# Schemat_JD.net
KiCad netlist of a schematic drawn in Altium Designer
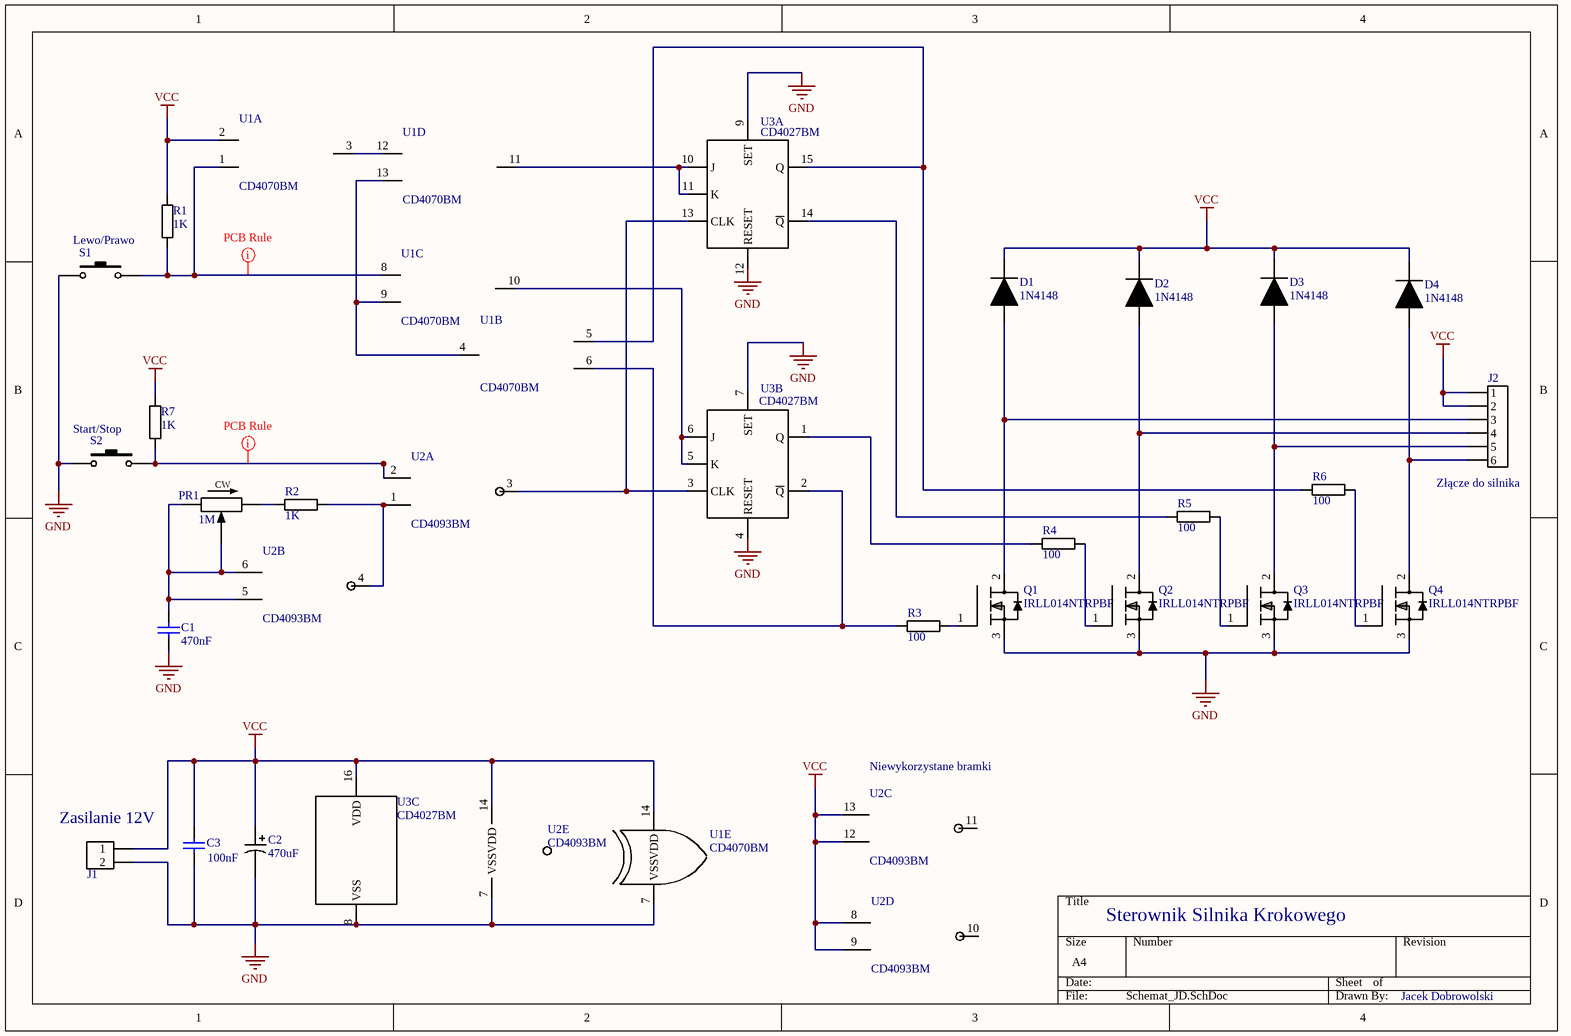
[diagram p0: Schemat_JD.SchDoc]

(export (version "E")
  (design (tool "Eeschema 10.0.6"))
  (components
    (comp (ref "C1")
      (value "470nF")
      (footprint "R0603_JD")
      (description "Capacitor (Semiconductor SIM Model)")
      (fields (field (name "Comment") "Cap Semi") (field (name "PUBLISHER") "Altium Limited"))
      (libsource (lib "Miscellaneous Devices") (part "Cap Semi"))
    )
    (comp (ref "C2")
      (value "470uF")
      (footprint "POL_CAP_JD")
      (fields (field (name "Comment") "ELECTROLYTIC_CAP_JD") (field (name "PUBLISHER") "Altium Limited"))
      (libsource (lib "SCH_LIB_JD") (part "ELECTROLYTIC_CAP_JD"))
    )
    (comp (ref "C3")
      (value "100nF")
      (footprint "R0603_JD")
      (description "Capacitor (Semiconductor SIM Model)")
      (fields (field (name "Comment") "Cap Semi") (field (name "PUBLISHER") "Altium Limited"))
      (libsource (lib "Miscellaneous Devices") (part "Cap Semi"))
    )
    (comp (ref "D1")
      (value "1N4148")
      (footprint "D0603_JD")
      (libsource (lib "SCH_LIB_JD") (part "1N4148_JD"))
    )
    (comp (ref "D2")
      (value "1N4148")
      (footprint "D0603_JD")
      (libsource (lib "SCH_LIB_JD") (part "1N4148_JD"))
    )
    (comp (ref "D3")
      (value "1N4148")
      (footprint "D0603_JD")
      (libsource (lib "SCH_LIB_JD") (part "1N4148_JD"))
    )
    (comp (ref "D4")
      (value "1N4148")
      (footprint "D0603_JD")
      (libsource (lib "SCH_LIB_JD") (part "1N4148_JD"))
    )
    (comp (ref "J1")
      (value "ARK_2.54")
      (footprint "ARK_DG308-2.54x2_JD")
      (libsource (lib "PADS_LIB_JD") (part "ARK2_2.54_JD"))
    )
    (comp (ref "J2")
      (value "GOLDPIN_HEADER")
      (footprint "GOLDPINx6_JD")
      (libsource (lib "PADS_LIB_JD") (part "GOLDPIN_JD"))
    )
    (comp (ref "PR1")
      (value "1M")
      (footprint "J_VISHAY_JD")
      (fields (field (name "Comment") "TRIMPOT"))
      (libsource (lib "PADS_LIB_JD") (part "POT_TS53J_JD"))
    )
    (comp (ref "Q1")
      (value "IRLL014NTRPBF")
      (footprint "SOT223_JD")
      (libsource (lib "PADS_LIB_JD") (part "IRLL014NTRPBF_JD"))
    )
    (comp (ref "Q2")
      (value "IRLL014NTRPBF")
      (footprint "SOT223_JD")
      (libsource (lib "PADS_LIB_JD") (part "IRLL014NTRPBF_JD"))
    )
    (comp (ref "Q3")
      (value "IRLL014NTRPBF")
      (footprint "SOT223_JD")
      (libsource (lib "PADS_LIB_JD") (part "IRLL014NTRPBF_JD"))
    )
    (comp (ref "Q4")
      (value "IRLL014NTRPBF")
      (footprint "SOT223_JD")
      (libsource (lib "PADS_LIB_JD") (part "IRLL014NTRPBF_JD"))
    )
    (comp (ref "R1")
      (value "1K")
      (footprint "R0603_JD")
      (description "Resistor")
      (fields (field (name "Comment") "RES_JD") (field (name "PUBLISHER") "Altium Limited"))
      (libsource (lib "SCH_LIB_JD") (part "RES_JD"))
    )
    (comp (ref "R2")
      (value "1K")
      (footprint "R0603_JD")
      (description "Resistor")
      (fields (field (name "Comment") "RES_JD") (field (name "PUBLISHER") "Altium Limited"))
      (libsource (lib "") (part "RES_JD_1"))
    )
    (comp (ref "R3")
      (value "100")
      (footprint "R0603_JD")
      (description "Resistor")
      (fields (field (name "Comment") "RES_JD") (field (name "PUBLISHER") "Altium Limited"))
      (libsource (lib "") (part "RES_JD_1"))
    )
    (comp (ref "R4")
      (value "100")
      (footprint "R0603_JD")
      (description "Resistor")
      (fields (field (name "Comment") "RES_JD") (field (name "PUBLISHER") "Altium Limited"))
      (libsource (lib "") (part "RES_JD_1"))
    )
    (comp (ref "R5")
      (value "100")
      (footprint "R0603_JD")
      (description "Resistor")
      (fields (field (name "Comment") "RES_JD") (field (name "PUBLISHER") "Altium Limited"))
      (libsource (lib "") (part "RES_JD_1"))
    )
    (comp (ref "R6")
      (value "100")
      (footprint "R0603_JD")
      (description "Resistor")
      (fields (field (name "Comment") "RES_JD") (field (name "PUBLISHER") "Altium Limited"))
      (libsource (lib "") (part "RES_JD_1"))
    )
    (comp (ref "R7")
      (value "1K")
      (footprint "R0603_JD")
      (description "Resistor")
      (fields (field (name "Comment") "RES_JD") (field (name "PUBLISHER") "Altium Limited"))
      (libsource (lib "SCH_LIB_JD") (part "RES_JD"))
    )
    (comp (ref "S1")
      (value "SWITCH_JD")
      (footprint "SPST_JD")
      (description "Switch")
      (fields (field (name "PUBLISHER") "Altium Limited"))
      (libsource (lib "SCH_LIB_JD") (part "SWITCH_JD"))
    )
    (comp (ref "S2")
      (value "SWITCH_JD")
      (footprint "SPST_JD")
      (description "Switch")
      (fields (field (name "PUBLISHER") "Altium Limited"))
      (libsource (lib "SCH_LIB_JD") (part "SWITCH_JD"))
    )
    (comp (ref "U1")
      (value "CD4070BM")
      (footprint "SO14_JD")
      (libsource (lib "PADS_LIB_JD") (part "CD4070BM_XOR_JD"))
    )
    (comp (ref "U2")
      (value "CD4093BM")
      (footprint "SO14_JD")
      (libsource (lib "SCH_LIB_JD") (part "CD4093BM_SCHMITT_JD"))
    )
    (comp (ref "U3")
      (value "CD4027BM")
      (footprint "SO16_JD")
      (libsource (lib "PADS_LIB_JD") (part "CD4027BM_JKFF_JD"))
    )
  )
  (nets
    (net (code "1") (name "GND") (class "Default")
      (node (ref "C1") (pin "1") (pinfunction "1_1") (pintype "passive"))
      (node (ref "C2") (pin "2") (pinfunction "2_2") (pintype "passive"))
      (node (ref "C3") (pin "1") (pinfunction "1_1") (pintype "passive"))
      (node (ref "J1") (pin "2") (pinfunction "2_2") (pintype "passive"))
      (node (ref "Q1") (pin "3") (pinfunction "S_3") (pintype "passive"))
      (node (ref "Q2") (pin "3") (pinfunction "S_3") (pintype "passive"))
      (node (ref "Q3") (pin "3") (pinfunction "S_3") (pintype "passive"))
      (node (ref "Q4") (pin "3") (pinfunction "S_3") (pintype "passive"))
      (node (ref "S1") (pin "1") (pinfunction "1_1") (pintype "passive"))
      (node (ref "S2") (pin "1") (pinfunction "1_1") (pintype "passive"))
      (node (ref "U1") (pin "7") (pinfunction "VSS_7") (pintype "passive"))
      (node (ref "U2") (pin "7") (pinfunction "VSS_7") (pintype "passive"))
      (node (ref "U3") (pin "12") (pinfunction "RESET_12") (pintype "passive"))
      (node (ref "U3") (pin "4") (pinfunction "RESET_4") (pintype "passive"))
      (node (ref "U3") (pin "7") (pinfunction "SET_7") (pintype "passive"))
      (node (ref "U3") (pin "8") (pinfunction "VSS_8") (pintype "passive"))
      (node (ref "U3") (pin "9") (pinfunction "SET_9") (pintype "passive"))
    )
    (net (code "2") (name "Net-(D1-Anode)") (class "Default")
      (node (ref "D1") (pin "A") (pinfunction "Anode_A") (pintype "passive"))
      (node (ref "J2") (pin "3") (pinfunction "3_3") (pintype "passive"))
      (node (ref "Q1") (pin "2") (pinfunction "D_2") (pintype "passive"))
    )
    (net (code "3") (name "Net-(D2-Anode)") (class "Default")
      (node (ref "D2") (pin "A") (pinfunction "Anode_A") (pintype "passive"))
      (node (ref "J2") (pin "4") (pinfunction "4_4") (pintype "passive"))
      (node (ref "Q2") (pin "2") (pinfunction "D_2") (pintype "passive"))
    )
    (net (code "4") (name "Net-(D3-Anode)") (class "Default")
      (node (ref "D3") (pin "A") (pinfunction "Anode_A") (pintype "passive"))
      (node (ref "J2") (pin "5") (pinfunction "5_5") (pintype "passive"))
      (node (ref "Q3") (pin "2") (pinfunction "D_2") (pintype "passive"))
    )
    (net (code "5") (name "Net-(D4-Anode)") (class "Default")
      (node (ref "D4") (pin "A") (pinfunction "Anode_A") (pintype "passive"))
      (node (ref "J2") (pin "6") (pinfunction "6_6") (pintype "passive"))
      (node (ref "Q4") (pin "2") (pinfunction "D_2") (pintype "passive"))
    )
    (net (code "6") (name "Net-(PR1-Pad3)") (class "Default")
      (node (ref "PR1") (pin "3") (pinfunction "3_3") (pintype "passive"))
      (node (ref "R2") (pin "1") (pinfunction "1_1") (pintype "passive"))
    )
    (net (code "7") (name "Net-(Q1-G)") (class "Default")
      (node (ref "Q1") (pin "1") (pinfunction "G_1") (pintype "passive"))
      (node (ref "R3") (pin "2") (pinfunction "2_2") (pintype "passive"))
    )
    (net (code "8") (name "Net-(Q2-G)") (class "Default")
      (node (ref "Q2") (pin "1") (pinfunction "G_1") (pintype "passive"))
      (node (ref "R4") (pin "2") (pinfunction "2_2") (pintype "passive"))
    )
    (net (code "9") (name "Net-(Q3-G)") (class "Default")
      (node (ref "Q3") (pin "1") (pinfunction "G_1") (pintype "passive"))
      (node (ref "R5") (pin "2") (pinfunction "2_2") (pintype "passive"))
    )
    (net (code "10") (name "Net-(Q4-G)") (class "Default")
      (node (ref "Q4") (pin "1") (pinfunction "G_1") (pintype "passive"))
      (node (ref "R6") (pin "2") (pinfunction "2_2") (pintype "passive"))
    )
    (net (code "11") (name "Net-(U1A-J)") (class "Default")
      (node (ref "U1") (pin "12") (pinfunction "G_12") (pintype "passive"))
      (node (ref "U1") (pin "3") (pinfunction "J_3") (pintype "passive"))
    )
    (net (code "12") (name "Net-(U1B-C)") (class "Default")
      (node (ref "R6") (pin "1") (pinfunction "1_1") (pintype "passive"))
      (node (ref "U1") (pin "5") (pinfunction "C_5") (pintype "passive"))
      (node (ref "U3") (pin "15") (pinfunction "Q_15") (pintype "passive"))
    )
    (net (code "13") (name "Net-(U1B-D)") (class "Default")
      (node (ref "R3") (pin "1") (pinfunction "1_1") (pintype "passive"))
      (node (ref "U1") (pin "6") (pinfunction "D_6") (pintype "passive"))
      (node (ref "U3") (pin "2") (pinfunction "~{Q}_2") (pintype "passive"))
    )
    (net (code "14") (name "Net-(U1B-K)") (class "Default")
      (node (ref "U1") (pin "13") (pinfunction "H_13") (pintype "passive"))
      (node (ref "U1") (pin "4") (pinfunction "K_4") (pintype "passive"))
      (node (ref "U1") (pin "9") (pinfunction "F_9") (pintype "passive"))
    )
    (net (code "15") (name "Net-(U1C-E)") (class "Default")
      (node (ref "R1") (pin "1") (pinfunction "1_1") (pintype "passive"))
      (node (ref "S1") (pin "3") (pinfunction "3_3") (pintype "passive"))
      (node (ref "U1") (pin "1") (pinfunction "A_1") (pintype "passive"))
      (node (ref "U1") (pin "8") (pinfunction "E_8") (pintype "passive"))
    )
    (net (code "16") (name "Net-(U1C-L)") (class "Default")
      (node (ref "U1") (pin "10") (pinfunction "L_10") (pintype "passive"))
      (node (ref "U3") (pin "5") (pinfunction "K_5") (pintype "passive"))
      (node (ref "U3") (pin "6") (pinfunction "J_6") (pintype "passive"))
    )
    (net (code "17") (name "Net-(U1D-M)") (class "Default")
      (node (ref "U1") (pin "11") (pinfunction "M_11") (pintype "passive"))
      (node (ref "U3") (pin "10") (pinfunction "J_10") (pintype "passive"))
      (node (ref "U3") (pin "11") (pinfunction "K_11") (pintype "passive"))
    )
    (net (code "18") (name "Net-(U2A-A)") (class "Default")
      (node (ref "R2") (pin "2") (pinfunction "2_2") (pintype "passive"))
      (node (ref "U2") (pin "1") (pinfunction "A_1") (pintype "passive"))
      (node (ref "U2") (pin "4") (pinfunction "K_4") (pintype "passive"))
    )
    (net (code "19") (name "Net-(U2A-B)") (class "Default")
      (node (ref "R7") (pin "1") (pinfunction "1_1") (pintype "passive"))
      (node (ref "S2") (pin "3") (pinfunction "3_3") (pintype "passive"))
      (node (ref "U2") (pin "2") (pinfunction "B_2") (pintype "passive"))
    )
    (net (code "20") (name "Net-(U2A-J)") (class "Default")
      (node (ref "U2") (pin "3") (pinfunction "J_3") (pintype "passive"))
      (node (ref "U3") (pin "13") (pinfunction "CLK_13") (pintype "passive"))
      (node (ref "U3") (pin "3") (pinfunction "CLK_3") (pintype "passive"))
    )
    (net (code "21") (name "Net-(U2B-C)") (class "Default")
      (node (ref "C1") (pin "2") (pinfunction "2_2") (pintype "passive"))
      (node (ref "PR1") (pin "1") (pinfunction "1_1") (pintype "passive"))
      (node (ref "PR1") (pin "2") (pinfunction "2_2") (pintype "passive"))
      (node (ref "U2") (pin "5") (pinfunction "C_5") (pintype "passive"))
      (node (ref "U2") (pin "6") (pinfunction "D_6") (pintype "passive"))
    )
    (net (code "22") (name "Net-(U3A-~{Q})") (class "Default")
      (node (ref "R5") (pin "1") (pinfunction "1_1") (pintype "passive"))
      (node (ref "U3") (pin "14") (pinfunction "~{Q}_14") (pintype "passive"))
    )
    (net (code "23") (name "Net-(U3B-Q)") (class "Default")
      (node (ref "R4") (pin "1") (pinfunction "1_1") (pintype "passive"))
      (node (ref "U3") (pin "1") (pinfunction "Q_1") (pintype "passive"))
    )
    (net (code "24") (name "VCC") (class "Default")
      (node (ref "C2") (pin "1") (pinfunction "1_1") (pintype "passive"))
      (node (ref "C3") (pin "2") (pinfunction "2_2") (pintype "passive"))
      (node (ref "D1") (pin "K") (pinfunction "Katode_K") (pintype "passive"))
      (node (ref "D2") (pin "K") (pinfunction "Katode_K") (pintype "passive"))
      (node (ref "D3") (pin "K") (pinfunction "Katode_K") (pintype "passive"))
      (node (ref "D4") (pin "K") (pinfunction "Katode_K") (pintype "passive"))
      (node (ref "J1") (pin "1") (pinfunction "1_1") (pintype "passive"))
      (node (ref "J2") (pin "1") (pinfunction "1_1") (pintype "passive"))
      (node (ref "J2") (pin "2") (pinfunction "2_2") (pintype "passive"))
      (node (ref "R1") (pin "2") (pinfunction "2_2") (pintype "passive"))
      (node (ref "R7") (pin "2") (pinfunction "2_2") (pintype "passive"))
      (node (ref "U1") (pin "14") (pinfunction "VDD_14") (pintype "passive"))
      (node (ref "U1") (pin "2") (pinfunction "A_2") (pintype "passive"))
      (node (ref "U2") (pin "12") (pinfunction "G_12") (pintype "passive"))
      (node (ref "U2") (pin "13") (pinfunction "H_13") (pintype "passive"))
      (node (ref "U2") (pin "14") (pinfunction "VDD_14") (pintype "passive"))
      (node (ref "U2") (pin "8") (pinfunction "E_8") (pintype "passive"))
      (node (ref "U2") (pin "9") (pinfunction "F_9") (pintype "passive"))
      (node (ref "U3") (pin "16") (pinfunction "VDD_16") (pintype "passive"))
    )
    (net (code "25") (name "unconnected-(U2C-M-Pad11)") (class "Default")
      (node (ref "U2") (pin "11") (pinfunction "M_11") (pintype "passive"))
    )
    (net (code "26") (name "unconnected-(U2D-L-Pad10)") (class "Default")
      (node (ref "U2") (pin "10") (pinfunction "L_10") (pintype "passive"))
    )
  )
)
